# bluetoot_relay.net
KiCad netlist of a schematic drawn in EAGLE
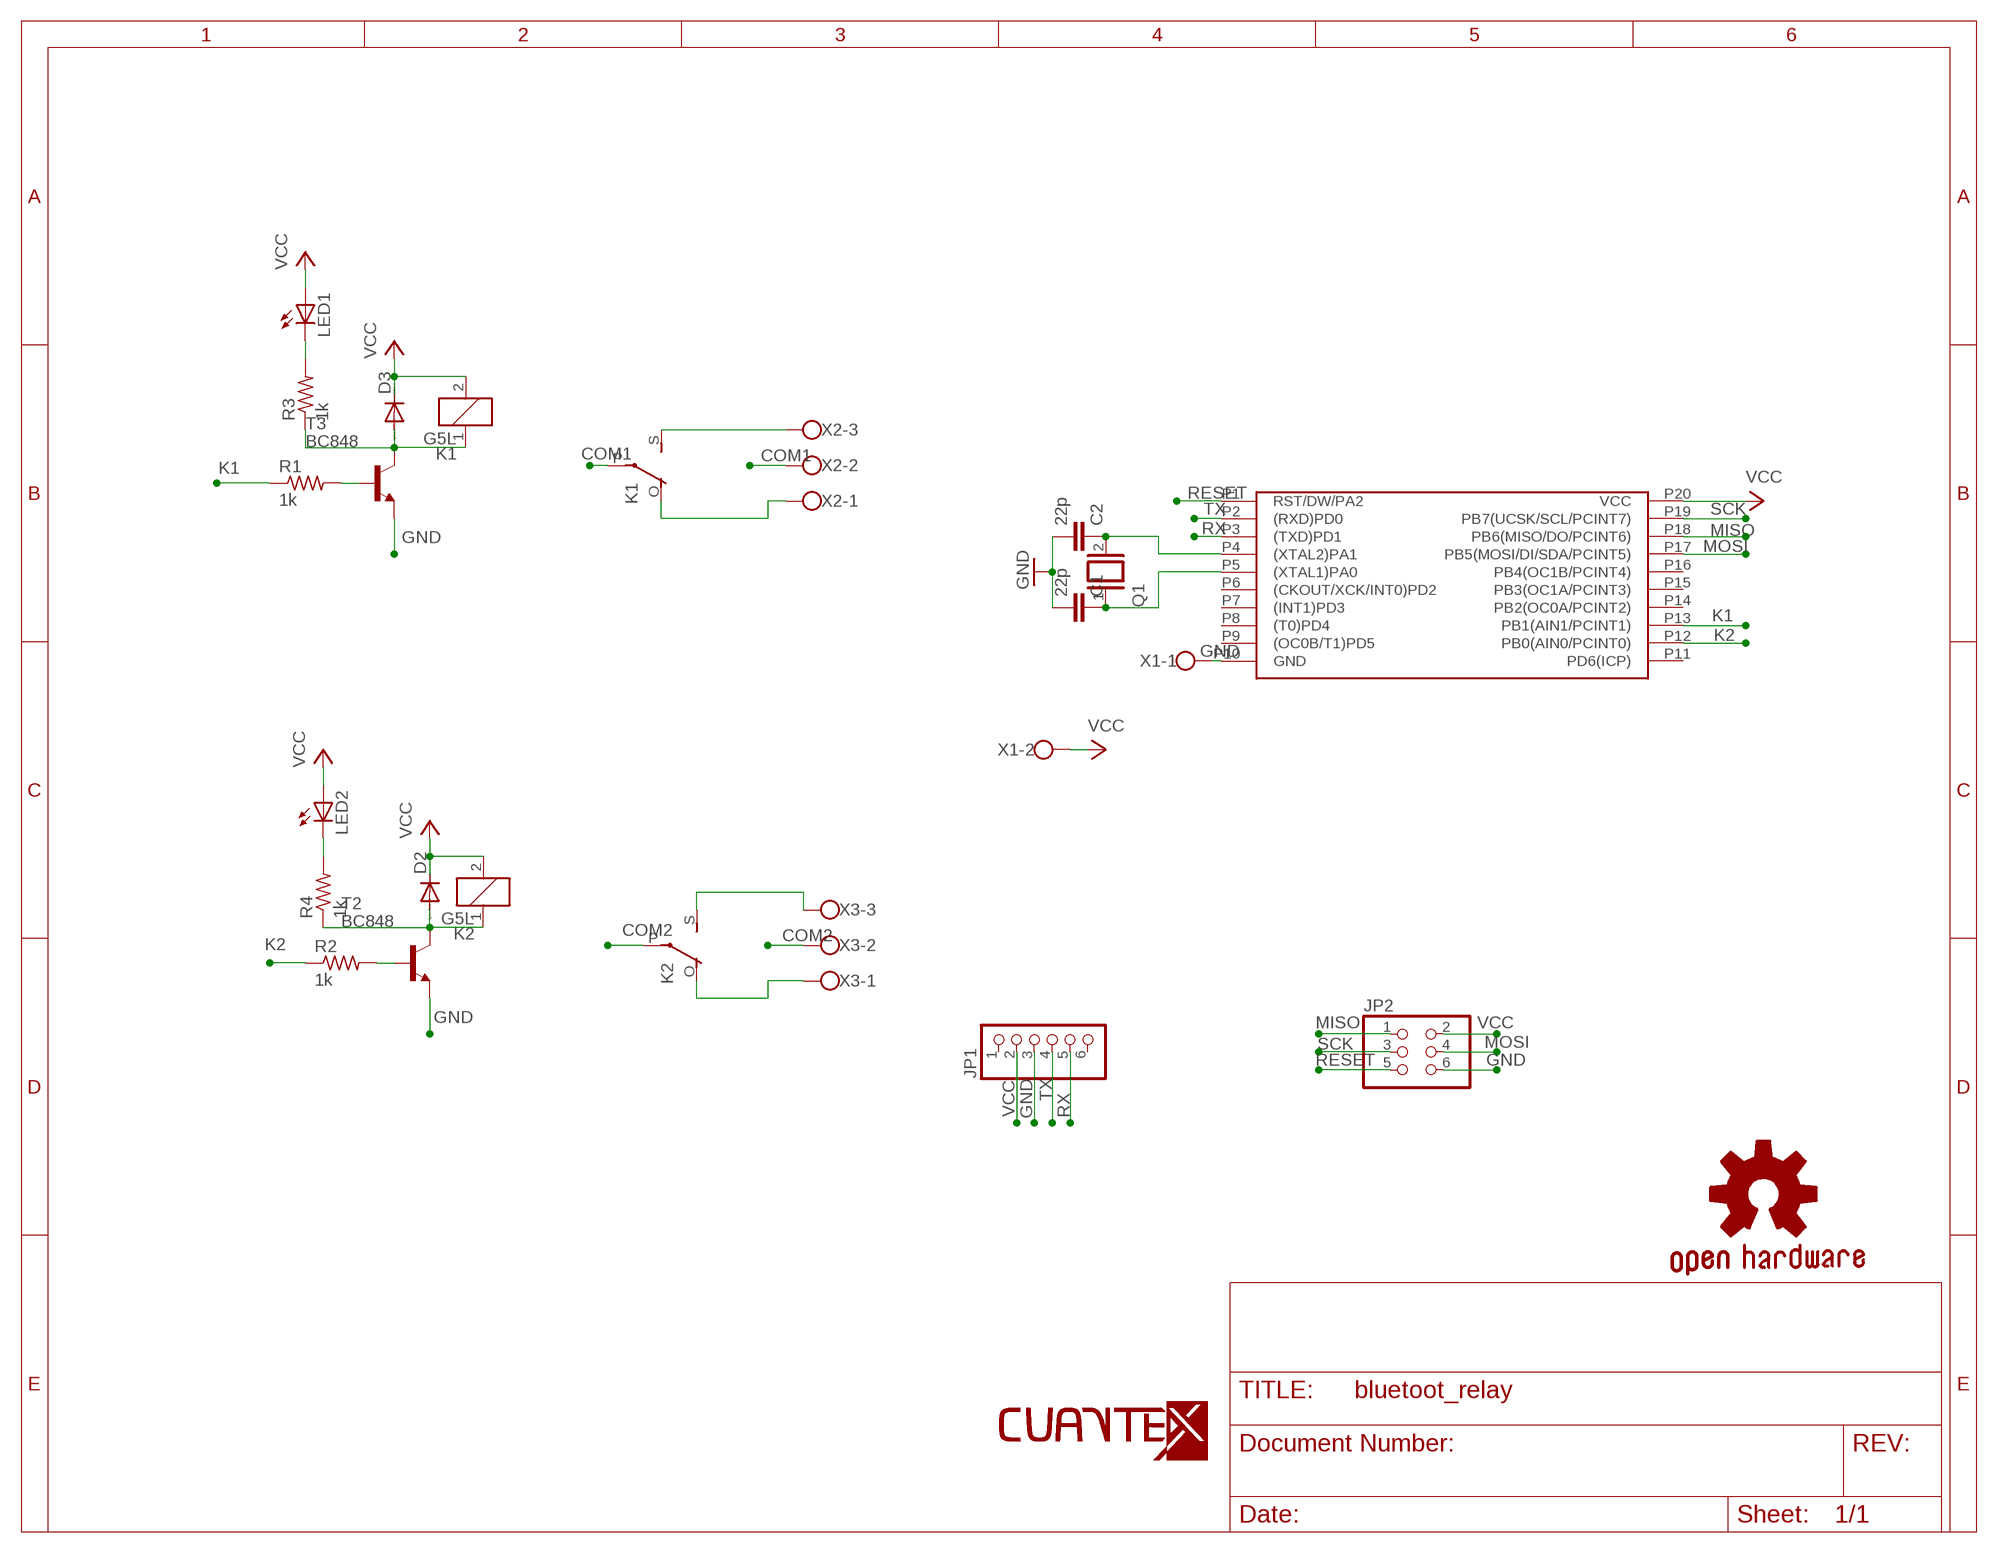
[diagram p0: schematic, sheet 1]

(export (version "E")
  (design (tool "Eeschema 10.0.6"))
  (components
    (comp (ref "C1")
      (value "22p")
      (footprint "eagle-import:C0603")
      (libsource (lib "eagle-import") (part "C-EUC0603"))
    )
    (comp (ref "C2")
      (value "22p")
      (footprint "eagle-import:C0603")
      (libsource (lib "eagle-import") (part "C-EUC0603"))
    )
    (comp (ref "D2")
      (value "DIODE-SMB")
      (footprint "eagle-import:SMB")
      (libsource (lib "eagle-import") (part "DIODE-SMB"))
    )
    (comp (ref "D3")
      (value "DIODE-SMB")
      (footprint "eagle-import:SMB")
      (libsource (lib "eagle-import") (part "DIODE-SMB"))
    )
    (comp (ref "GOLD_ORB_SM1")
      (value "OSHWLOGO_GOLD_ORB_SM")
      (footprint "eagle-import:OSHW2")
      (libsource (lib "eagle-import") (part "OSHWLOGO_GOLD_ORB_SM"))
    )
    (comp (ref "JP1")
      (value "PINHD-1X6")
      (footprint "eagle-import:1X06")
      (libsource (lib "eagle-import") (part "PINHD-1X6"))
    )
    (comp (ref "JP2")
      (value "PINHD-2X3")
      (footprint "eagle-import:2X03")
      (libsource (lib "eagle-import") (part "PINHD-2X3"))
    )
    (comp (ref "K1")
      (value "G5L")
      (footprint "eagle-import:G5LE")
      (libsource (lib "eagle-import") (part "G5L"))
    )
    (comp (ref "K2")
      (value "G5L")
      (footprint "eagle-import:G5LE")
      (libsource (lib "eagle-import") (part "G5L"))
    )
    (comp (ref "LED1")
      (value "LED0603")
      (footprint "eagle-import:LED-0603")
      (libsource (lib "eagle-import") (part "LED0603"))
    )
    (comp (ref "LED2")
      (value "LED0603")
      (footprint "eagle-import:LED-0603")
      (libsource (lib "eagle-import") (part "LED0603"))
    )
    (comp (ref "Q1")
      (value "XTAL/S")
      (footprint "eagle-import:QS")
      (libsource (lib "eagle-import") (part "XTAL/S"))
    )
    (comp (ref "R1")
      (value "1k")
      (footprint "eagle-import:R0603")
      (libsource (lib "eagle-import") (part "R-US_R0603"))
    )
    (comp (ref "R2")
      (value "1k")
      (footprint "eagle-import:R0603")
      (libsource (lib "eagle-import") (part "R-US_R0603"))
    )
    (comp (ref "R3")
      (value "1k")
      (footprint "eagle-import:R0603")
      (libsource (lib "eagle-import") (part "R-US_R0603"))
    )
    (comp (ref "R4")
      (value "1k")
      (footprint "eagle-import:R0603")
      (libsource (lib "eagle-import") (part "R-US_R0603"))
    )
    (comp (ref "T2")
      (value "BC848")
      (footprint "eagle-import:SOT23")
      (libsource (lib "eagle-import") (part "BC848"))
    )
    (comp (ref "T3")
      (value "BC848")
      (footprint "eagle-import:SOT23")
      (libsource (lib "eagle-import") (part "BC848"))
    )
    (comp (ref "U$1")
      (value "ATTYNY2313/V")
      (footprint "eagle-import:SOIC")
      (libsource (lib "eagle-import") (part "ATTYNY2313/V"))
    )
    (comp (ref "U$3")
      (value "LOGO-TOP-20MM")
      (footprint "eagle-import:C-0")
      (libsource (lib "eagle-import") (part "LOGO-TOP-20MM"))
    )
    (comp (ref "U$4")
      (value "LOGO-TOP-50MM")
      (footprint "eagle-import:C-3")
      (libsource (lib "eagle-import") (part "LOGO-TOP-50MM"))
    )
    (comp (ref "X1")
      (value "W237-102")
      (footprint "eagle-import:W237-102")
      (fields (field (name "MPN") "237-102"))
      (libsource (lib "eagle-import") (part "W237-102"))
    )
    (comp (ref "X2")
      (value "W237-103")
      (footprint "eagle-import:W237-103")
      (fields (field (name "MPN") "237-103"))
      (libsource (lib "eagle-import") (part "W237-103"))
    )
    (comp (ref "X3")
      (value "W237-103")
      (footprint "eagle-import:W237-103")
      (fields (field (name "MPN") "237-103"))
      (libsource (lib "eagle-import") (part "W237-103"))
    )
  )
  (nets
    (net (code "1") (name "/COM1") (class "Default")
      (node (ref "K1") (pin "P") (pinfunction "P_P") (pintype "passive"))
      (node (ref "X2") (pin "2") (pinfunction "KL_2") (pintype "passive"))
    )
    (net (code "2") (name "/COM2") (class "Default")
      (node (ref "K2") (pin "P") (pinfunction "P_P") (pintype "passive"))
      (node (ref "X3") (pin "2") (pinfunction "KL_2") (pintype "passive"))
    )
    (net (code "3") (name "/K1") (class "Default")
      (node (ref "R1") (pin "1") (pinfunction "1_1") (pintype "passive"))
      (node (ref "U$1") (pin "P13") (pinfunction "PB1(AIN1/PCINT1)_P13") (pintype "bidirectional"))
    )
    (net (code "4") (name "/K2") (class "Default")
      (node (ref "R2") (pin "1") (pinfunction "1_1") (pintype "passive"))
      (node (ref "U$1") (pin "P12") (pinfunction "PB0(AIN0/PCINT0)_P12") (pintype "bidirectional"))
    )
    (net (code "5") (name "/MISO") (class "Default")
      (node (ref "JP2") (pin "1") (pinfunction "1_1") (pintype "passive"))
      (node (ref "U$1") (pin "P18") (pinfunction "PB6(MISO/DO/PCINT6)_P18") (pintype "bidirectional"))
    )
    (net (code "6") (name "/MOSI") (class "Default")
      (node (ref "JP2") (pin "4") (pinfunction "4_4") (pintype "passive"))
      (node (ref "U$1") (pin "P17") (pinfunction "PB5(MOSI/DI/SDA/PCINT5)_P17") (pintype "bidirectional"))
    )
    (net (code "7") (name "/RESET") (class "Default")
      (node (ref "JP2") (pin "5") (pinfunction "5_5") (pintype "passive"))
      (node (ref "U$1") (pin "P1") (pinfunction "RST/DW/PA2_P1") (pintype "bidirectional"))
    )
    (net (code "8") (name "/RX") (class "Default")
      (node (ref "JP1") (pin "5") (pinfunction "5_5") (pintype "passive"))
      (node (ref "U$1") (pin "P3") (pinfunction "(TXD)PD1_P3") (pintype "bidirectional"))
    )
    (net (code "9") (name "/SCK") (class "Default")
      (node (ref "JP2") (pin "3") (pinfunction "3_3") (pintype "passive"))
      (node (ref "U$1") (pin "P19") (pinfunction "PB7(UCSK/SCL/PCINT7)_P19") (pintype "bidirectional"))
    )
    (net (code "10") (name "/TX") (class "Default")
      (node (ref "JP1") (pin "4") (pinfunction "4_4") (pintype "passive"))
      (node (ref "U$1") (pin "P2") (pinfunction "(RXD)PD0_P2") (pintype "bidirectional"))
    )
    (net (code "11") (name "GND") (class "Default")
      (node (ref "C1") (pin "2") (pinfunction "2_2") (pintype "passive"))
      (node (ref "C2") (pin "2") (pinfunction "2_2") (pintype "passive"))
      (node (ref "JP1") (pin "3") (pinfunction "3_3") (pintype "passive"))
      (node (ref "JP2") (pin "6") (pinfunction "6_6") (pintype "passive"))
      (node (ref "T2") (pin "2") (pinfunction "E_2") (pintype "passive"))
      (node (ref "T3") (pin "2") (pinfunction "E_2") (pintype "passive"))
      (node (ref "U$1") (pin "P10") (pinfunction "GND_P10") (pintype "bidirectional"))
      (node (ref "X1") (pin "1") (pinfunction "KL_1") (pintype "passive"))
    )
    (net (code "12") (name "Net-(LED1-PadC)") (class "Default")
      (node (ref "LED1") (pin "C") (pinfunction "C_C") (pintype "passive"))
      (node (ref "R3") (pin "2") (pinfunction "2_2") (pintype "passive"))
    )
    (net (code "13") (name "Net-(LED2-PadC)") (class "Default")
      (node (ref "LED2") (pin "C") (pinfunction "C_C") (pintype "passive"))
      (node (ref "R4") (pin "2") (pinfunction "2_2") (pintype "passive"))
    )
    (net (code "14") (name "Net-(T2-B)") (class "Default")
      (node (ref "R2") (pin "2") (pinfunction "2_2") (pintype "passive"))
      (node (ref "T2") (pin "1") (pinfunction "B_1") (pintype "passive"))
    )
    (net (code "15") (name "Net-(T2-C)") (class "Default")
      (node (ref "D2") (pin "A") (pinfunction "A_A") (pintype "passive"))
      (node (ref "K2") (pin "1") (pinfunction "1_1") (pintype "passive"))
      (node (ref "R4") (pin "1") (pinfunction "1_1") (pintype "passive"))
      (node (ref "T2") (pin "3") (pinfunction "C_3") (pintype "passive"))
    )
    (net (code "16") (name "Net-(T3-B)") (class "Default")
      (node (ref "R1") (pin "2") (pinfunction "2_2") (pintype "passive"))
      (node (ref "T3") (pin "1") (pinfunction "B_1") (pintype "passive"))
    )
    (net (code "17") (name "Net-(T3-C)") (class "Default")
      (node (ref "D3") (pin "A") (pinfunction "A_A") (pintype "passive"))
      (node (ref "K1") (pin "1") (pinfunction "1_1") (pintype "passive"))
      (node (ref "R3") (pin "1") (pinfunction "1_1") (pintype "passive"))
      (node (ref "T3") (pin "3") (pinfunction "C_3") (pintype "passive"))
    )
    (net (code "18") (name "Net-(U$1-(XTAL1)PA0)") (class "Default")
      (node (ref "C1") (pin "1") (pinfunction "1_1") (pintype "passive"))
      (node (ref "Q1") (pin "1") (pinfunction "1_1") (pintype "passive"))
      (node (ref "U$1") (pin "P5") (pinfunction "(XTAL1)PA0_P5") (pintype "bidirectional"))
    )
    (net (code "19") (name "Net-(U$1-(XTAL2)PA1)") (class "Default")
      (node (ref "C2") (pin "1") (pinfunction "1_1") (pintype "passive"))
      (node (ref "Q1") (pin "2") (pinfunction "2_2") (pintype "passive"))
      (node (ref "U$1") (pin "P4") (pinfunction "(XTAL2)PA1_P4") (pintype "bidirectional"))
    )
    (net (code "20") (name "Net-(X2A-KL)") (class "Default")
      (node (ref "K1") (pin "O") (pinfunction "O_O") (pintype "passive"))
      (node (ref "X2") (pin "1") (pinfunction "KL_1") (pintype "passive"))
    )
    (net (code "21") (name "Net-(X2C-KL)") (class "Default")
      (node (ref "K1") (pin "S") (pinfunction "S_S") (pintype "passive"))
      (node (ref "X2") (pin "3") (pinfunction "KL_3") (pintype "passive"))
    )
    (net (code "22") (name "Net-(X3A-KL)") (class "Default")
      (node (ref "K2") (pin "O") (pinfunction "O_O") (pintype "passive"))
      (node (ref "X3") (pin "1") (pinfunction "KL_1") (pintype "passive"))
    )
    (net (code "23") (name "Net-(X3C-KL)") (class "Default")
      (node (ref "K2") (pin "S") (pinfunction "S_S") (pintype "passive"))
      (node (ref "X3") (pin "3") (pinfunction "KL_3") (pintype "passive"))
    )
    (net (code "24") (name "VCC") (class "Default")
      (node (ref "D2") (pin "C") (pinfunction "C_C") (pintype "passive"))
      (node (ref "D3") (pin "C") (pinfunction "C_C") (pintype "passive"))
      (node (ref "JP1") (pin "2") (pinfunction "2_2") (pintype "passive"))
      (node (ref "JP2") (pin "2") (pinfunction "2_2") (pintype "passive"))
      (node (ref "K1") (pin "2") (pinfunction "2_2") (pintype "passive"))
      (node (ref "K2") (pin "2") (pinfunction "2_2") (pintype "passive"))
      (node (ref "LED1") (pin "A") (pinfunction "A_A") (pintype "passive"))
      (node (ref "LED2") (pin "A") (pinfunction "A_A") (pintype "passive"))
      (node (ref "U$1") (pin "P20") (pinfunction "VCC_P20") (pintype "bidirectional"))
      (node (ref "X1") (pin "2") (pinfunction "KL_2") (pintype "passive"))
    )
    (net (code "25") (name "unconnected-(JP1-Pad1)") (class "Default")
      (node (ref "JP1") (pin "1") (pinfunction "1_1") (pintype "passive"))
    )
    (net (code "26") (name "unconnected-(JP1-Pad6)") (class "Default")
      (node (ref "JP1") (pin "6") (pinfunction "6_6") (pintype "passive"))
    )
    (net (code "27") (name "unconnected-(U$1-(CKOUT{slash}XCK{slash}INT0)PD2-PadP6)") (class "Default")
      (node (ref "U$1") (pin "P6") (pinfunction "(CKOUT/XCK/INT0)PD2_P6") (pintype "bidirectional"))
    )
    (net (code "28") (name "unconnected-(U$1-(INT1)PD3-PadP7)") (class "Default")
      (node (ref "U$1") (pin "P7") (pinfunction "(INT1)PD3_P7") (pintype "bidirectional"))
    )
    (net (code "29") (name "unconnected-(U$1-(OC0B{slash}T1)PD5-PadP9)") (class "Default")
      (node (ref "U$1") (pin "P9") (pinfunction "(OC0B/T1)PD5_P9") (pintype "bidirectional"))
    )
    (net (code "30") (name "unconnected-(U$1-(T0)PD4-PadP8)") (class "Default")
      (node (ref "U$1") (pin "P8") (pinfunction "(T0)PD4_P8") (pintype "bidirectional"))
    )
    (net (code "31") (name "unconnected-(U$1-PB2(OC0A{slash}PCINT2)-PadP14)") (class "Default")
      (node (ref "U$1") (pin "P14") (pinfunction "PB2(OC0A/PCINT2)_P14") (pintype "bidirectional"))
    )
    (net (code "32") (name "unconnected-(U$1-PB3(OC1A{slash}PCINT3)-PadP15)") (class "Default")
      (node (ref "U$1") (pin "P15") (pinfunction "PB3(OC1A/PCINT3)_P15") (pintype "bidirectional"))
    )
    (net (code "33") (name "unconnected-(U$1-PB4(OC1B{slash}PCINT4)-PadP16)") (class "Default")
      (node (ref "U$1") (pin "P16") (pinfunction "PB4(OC1B/PCINT4)_P16") (pintype "bidirectional"))
    )
    (net (code "34") (name "unconnected-(U$1-PD6(ICP)-PadP11)") (class "Default")
      (node (ref "U$1") (pin "P11") (pinfunction "PD6(ICP)_P11") (pintype "bidirectional"))
    )
  )
)
